# StackBreakoutConnection_4layers_V1_0_wit.net
KiCad netlist of a schematic drawn in EAGLE
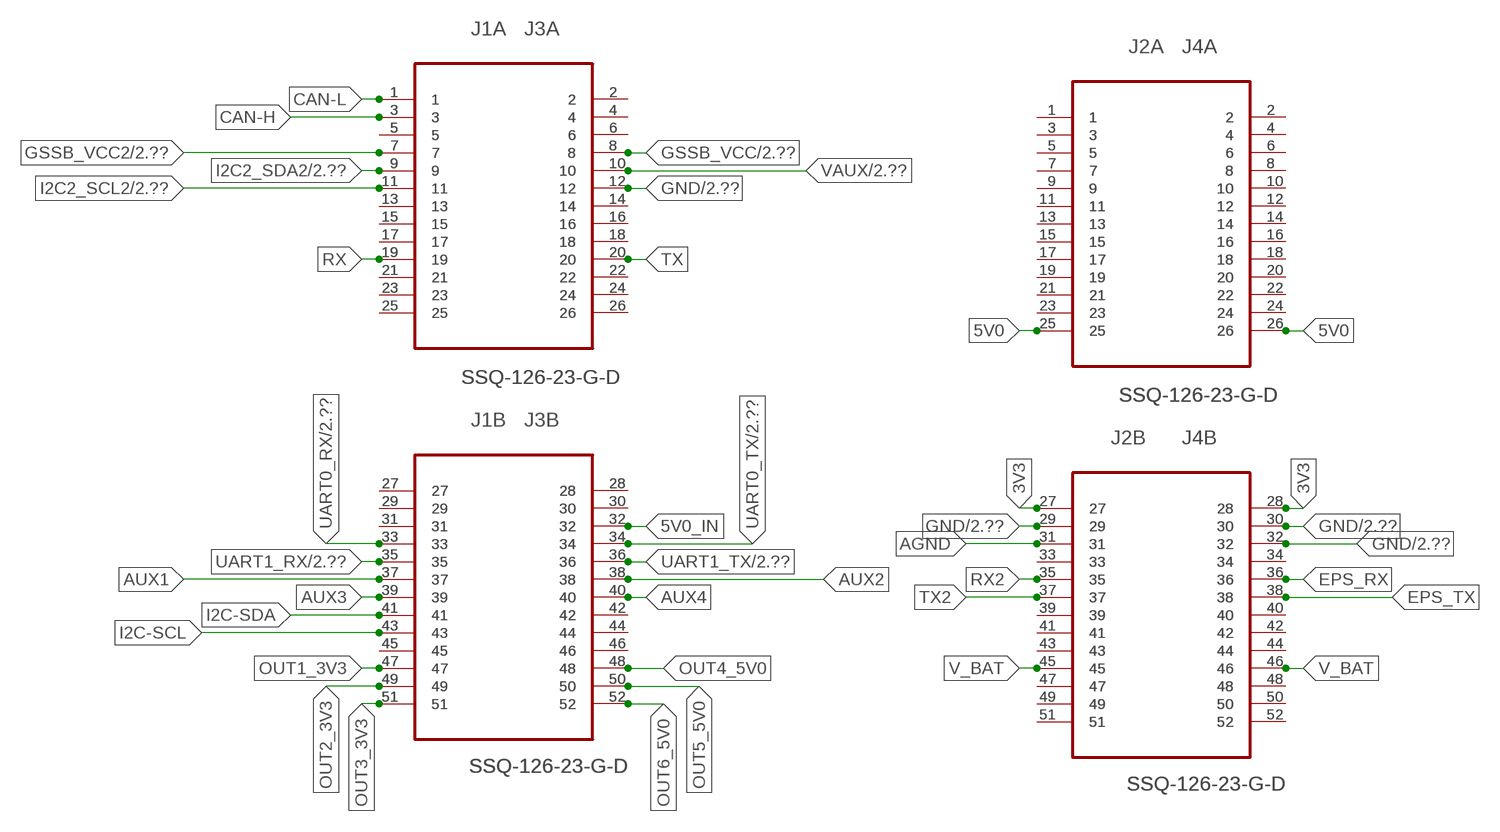
[diagram p0: schematic, sheet 1]
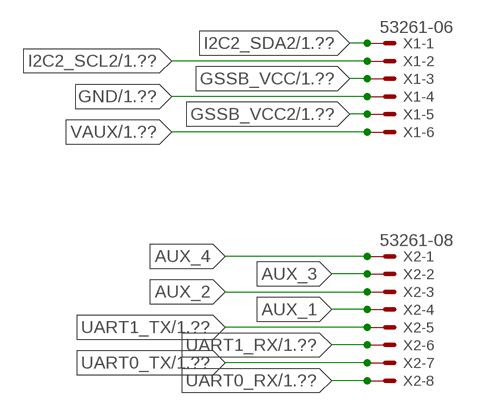
[diagram p1: schematic, sheet 2]

(export (version "E")
  (design (tool "Eeschema 10.0.6"))
  (components
    (comp (ref "X1")
      (value "53261-06")
      (footprint "eagle-import:53261-06")
      (fields (field (name "MF") "MOLEX"))
      (libsource (lib "eagle-import") (part "53?-06261"))
    )
    (comp (ref "X2")
      (value "53261-08")
      (footprint "eagle-import:53261-08")
      (fields (field (name "MF") "MOLEX"))
      (libsource (lib "eagle-import") (part "53?-08261"))
    )
    (comp (ref "J1")
      (value "SSQ-126-23-G-D")
      (footprint "eagle-import:SAMTEC_SSQ-126-23-G-D")
      (libsource (lib "eagle-import") (part "SSQ-126-23-G-D"))
    )
    (comp (ref "J2")
      (value "SSQ-126-23-G-D")
      (footprint "eagle-import:SAMTEC_SSQ-126-23-G-D")
      (libsource (lib "eagle-import") (part "SSQ-126-23-G-D"))
    )
    (comp (ref "J3")
      (value "SSQ-126-23-G-D")
      (footprint "eagle-import:SAMTEC_SSQ-126-23-G-D")
      (libsource (lib "eagle-import") (part "SSQ-126-23-G-D"))
    )
    (comp (ref "J4")
      (value "SSQ-126-23-G-D")
      (footprint "eagle-import:SAMTEC_SSQ-126-23-G-D")
      (libsource (lib "eagle-import") (part "SSQ-126-23-G-D"))
    )
  )
  (nets
    (net (code "1") (name "3V3") (class "Default")
      (node (ref "J2") (pin "27") (pinfunction "27_27") (pintype "passive"))
      (node (ref "J2") (pin "28") (pinfunction "28_28") (pintype "passive"))
      (node (ref "J4") (pin "27") (pinfunction "27_27") (pintype "passive"))
      (node (ref "J4") (pin "28") (pinfunction "28_28") (pintype "passive"))
    )
    (net (code "2") (name "5V0") (class "Default")
      (node (ref "J2") (pin "25") (pinfunction "25_25") (pintype "passive"))
      (node (ref "J2") (pin "26") (pinfunction "26_26") (pintype "passive"))
      (node (ref "J4") (pin "25") (pinfunction "25_25") (pintype "passive"))
      (node (ref "J4") (pin "26") (pinfunction "26_26") (pintype "passive"))
    )
    (net (code "3") (name "5V0_IN") (class "Default")
      (node (ref "J1") (pin "32") (pinfunction "32_32") (pintype "passive"))
      (node (ref "J3") (pin "32") (pinfunction "32_32") (pintype "passive"))
    )
    (net (code "4") (name "AGND") (class "Default")
      (node (ref "J2") (pin "31") (pinfunction "31_31") (pintype "passive"))
      (node (ref "J4") (pin "31") (pinfunction "31_31") (pintype "passive"))
    )
    (net (code "5") (name "AUX1") (class "Default")
      (node (ref "J1") (pin "37") (pinfunction "37_37") (pintype "passive"))
      (node (ref "J3") (pin "37") (pinfunction "37_37") (pintype "passive"))
    )
    (net (code "6") (name "AUX2") (class "Default")
      (node (ref "J1") (pin "38") (pinfunction "38_38") (pintype "passive"))
      (node (ref "J3") (pin "38") (pinfunction "38_38") (pintype "passive"))
    )
    (net (code "7") (name "AUX3") (class "Default")
      (node (ref "J1") (pin "39") (pinfunction "39_39") (pintype "passive"))
      (node (ref "J3") (pin "39") (pinfunction "39_39") (pintype "passive"))
    )
    (net (code "8") (name "AUX4") (class "Default")
      (node (ref "J1") (pin "40") (pinfunction "40_40") (pintype "passive"))
      (node (ref "J3") (pin "40") (pinfunction "40_40") (pintype "passive"))
    )
    (net (code "9") (name "AUX_1") (class "Default")
      (node (ref "X2") (pin "4") (pinfunction "S_4") (pintype "passive"))
    )
    (net (code "10") (name "AUX_2") (class "Default")
      (node (ref "X2") (pin "3") (pinfunction "S_3") (pintype "passive"))
    )
    (net (code "11") (name "AUX_3") (class "Default")
      (node (ref "X2") (pin "2") (pinfunction "S_2") (pintype "passive"))
    )
    (net (code "12") (name "AUX_4") (class "Default")
      (node (ref "X2") (pin "1") (pinfunction "S_1") (pintype "passive"))
    )
    (net (code "13") (name "CAN-H") (class "Default")
      (node (ref "J1") (pin "3") (pinfunction "3_3") (pintype "passive"))
      (node (ref "J3") (pin "3") (pinfunction "3_3") (pintype "passive"))
    )
    (net (code "14") (name "CAN-L") (class "Default")
      (node (ref "J1") (pin "1") (pinfunction "1_1") (pintype "passive"))
      (node (ref "J3") (pin "1") (pinfunction "1_1") (pintype "passive"))
    )
    (net (code "15") (name "EPS_RX") (class "Default")
      (node (ref "J2") (pin "36") (pinfunction "36_36") (pintype "passive"))
      (node (ref "J4") (pin "36") (pinfunction "36_36") (pintype "passive"))
    )
    (net (code "16") (name "EPS_TX") (class "Default")
      (node (ref "J2") (pin "38") (pinfunction "38_38") (pintype "passive"))
      (node (ref "J4") (pin "38") (pinfunction "38_38") (pintype "passive"))
    )
    (net (code "17") (name "GND") (class "Default")
      (node (ref "J1") (pin "12") (pinfunction "12_12") (pintype "passive"))
      (node (ref "J2") (pin "29") (pinfunction "29_29") (pintype "passive"))
      (node (ref "J2") (pin "30") (pinfunction "30_30") (pintype "passive"))
      (node (ref "J2") (pin "32") (pinfunction "32_32") (pintype "passive"))
      (node (ref "J3") (pin "12") (pinfunction "12_12") (pintype "passive"))
      (node (ref "J4") (pin "29") (pinfunction "29_29") (pintype "passive"))
      (node (ref "J4") (pin "30") (pinfunction "30_30") (pintype "passive"))
      (node (ref "J4") (pin "32") (pinfunction "32_32") (pintype "passive"))
      (node (ref "X1") (pin "4") (pinfunction "S_4") (pintype "passive"))
    )
    (net (code "18") (name "GSSB_VCC") (class "Default")
      (node (ref "J1") (pin "8") (pinfunction "8_8") (pintype "passive"))
      (node (ref "J3") (pin "8") (pinfunction "8_8") (pintype "passive"))
      (node (ref "X1") (pin "3") (pinfunction "S_3") (pintype "passive"))
    )
    (net (code "19") (name "GSSB_VCC2") (class "Default")
      (node (ref "J1") (pin "7") (pinfunction "7_7") (pintype "passive"))
      (node (ref "J3") (pin "7") (pinfunction "7_7") (pintype "passive"))
      (node (ref "X1") (pin "5") (pinfunction "S_5") (pintype "passive"))
    )
    (net (code "20") (name "I2C-SCL") (class "Default")
      (node (ref "J1") (pin "43") (pinfunction "43_43") (pintype "passive"))
      (node (ref "J3") (pin "43") (pinfunction "43_43") (pintype "passive"))
    )
    (net (code "21") (name "I2C-SDA") (class "Default")
      (node (ref "J1") (pin "41") (pinfunction "41_41") (pintype "passive"))
      (node (ref "J3") (pin "41") (pinfunction "41_41") (pintype "passive"))
    )
    (net (code "22") (name "I2C2_SCL2") (class "Default")
      (node (ref "J1") (pin "11") (pinfunction "11_11") (pintype "passive"))
      (node (ref "J3") (pin "11") (pinfunction "11_11") (pintype "passive"))
      (node (ref "X1") (pin "2") (pinfunction "S_2") (pintype "passive"))
    )
    (net (code "23") (name "I2C2_SDA2") (class "Default")
      (node (ref "J1") (pin "9") (pinfunction "9_9") (pintype "passive"))
      (node (ref "J3") (pin "9") (pinfunction "9_9") (pintype "passive"))
      (node (ref "X1") (pin "1") (pinfunction "S_1") (pintype "passive"))
    )
    (net (code "24") (name "Net-(J1-Pad2)") (class "Default")
      (node (ref "J1") (pin "2") (pinfunction "2_2") (pintype "passive"))
      (node (ref "J3") (pin "2") (pinfunction "2_2") (pintype "passive"))
    )
    (net (code "25") (name "Net-(J1-Pad4)") (class "Default")
      (node (ref "J1") (pin "4") (pinfunction "4_4") (pintype "passive"))
      (node (ref "J3") (pin "4") (pinfunction "4_4") (pintype "passive"))
    )
    (net (code "26") (name "Net-(J1-Pad5)") (class "Default")
      (node (ref "J1") (pin "5") (pinfunction "5_5") (pintype "passive"))
      (node (ref "J3") (pin "5") (pinfunction "5_5") (pintype "passive"))
    )
    (net (code "27") (name "Net-(J1-Pad6)") (class "Default")
      (node (ref "J1") (pin "6") (pinfunction "6_6") (pintype "passive"))
      (node (ref "J3") (pin "6") (pinfunction "6_6") (pintype "passive"))
    )
    (net (code "28") (name "Net-(J1-Pad13)") (class "Default")
      (node (ref "J1") (pin "13") (pinfunction "13_13") (pintype "passive"))
      (node (ref "J3") (pin "13") (pinfunction "13_13") (pintype "passive"))
    )
    (net (code "29") (name "Net-(J1-Pad14)") (class "Default")
      (node (ref "J1") (pin "14") (pinfunction "14_14") (pintype "passive"))
      (node (ref "J3") (pin "14") (pinfunction "14_14") (pintype "passive"))
    )
    (net (code "30") (name "Net-(J1-Pad15)") (class "Default")
      (node (ref "J1") (pin "15") (pinfunction "15_15") (pintype "passive"))
      (node (ref "J3") (pin "15") (pinfunction "15_15") (pintype "passive"))
    )
    (net (code "31") (name "Net-(J1-Pad16)") (class "Default")
      (node (ref "J1") (pin "16") (pinfunction "16_16") (pintype "passive"))
      (node (ref "J3") (pin "16") (pinfunction "16_16") (pintype "passive"))
    )
    (net (code "32") (name "Net-(J1-Pad17)") (class "Default")
      (node (ref "J1") (pin "17") (pinfunction "17_17") (pintype "passive"))
      (node (ref "J3") (pin "17") (pinfunction "17_17") (pintype "passive"))
    )
    (net (code "33") (name "Net-(J1-Pad18)") (class "Default")
      (node (ref "J1") (pin "18") (pinfunction "18_18") (pintype "passive"))
      (node (ref "J3") (pin "18") (pinfunction "18_18") (pintype "passive"))
    )
    (net (code "34") (name "Net-(J1-Pad21)") (class "Default")
      (node (ref "J1") (pin "21") (pinfunction "21_21") (pintype "passive"))
      (node (ref "J3") (pin "21") (pinfunction "21_21") (pintype "passive"))
    )
    (net (code "35") (name "Net-(J1-Pad22)") (class "Default")
      (node (ref "J1") (pin "22") (pinfunction "22_22") (pintype "passive"))
      (node (ref "J3") (pin "22") (pinfunction "22_22") (pintype "passive"))
    )
    (net (code "36") (name "Net-(J1-Pad23)") (class "Default")
      (node (ref "J1") (pin "23") (pinfunction "23_23") (pintype "passive"))
      (node (ref "J3") (pin "23") (pinfunction "23_23") (pintype "passive"))
    )
    (net (code "37") (name "Net-(J1-Pad24)") (class "Default")
      (node (ref "J1") (pin "24") (pinfunction "24_24") (pintype "passive"))
      (node (ref "J3") (pin "24") (pinfunction "24_24") (pintype "passive"))
    )
    (net (code "38") (name "Net-(J1-Pad25)") (class "Default")
      (node (ref "J1") (pin "25") (pinfunction "25_25") (pintype "passive"))
      (node (ref "J3") (pin "25") (pinfunction "25_25") (pintype "passive"))
    )
    (net (code "39") (name "Net-(J1-Pad26)") (class "Default")
      (node (ref "J1") (pin "26") (pinfunction "26_26") (pintype "passive"))
      (node (ref "J3") (pin "26") (pinfunction "26_26") (pintype "passive"))
    )
    (net (code "40") (name "Net-(J1-Pad27)") (class "Default")
      (node (ref "J1") (pin "27") (pinfunction "27_27") (pintype "passive"))
      (node (ref "J3") (pin "27") (pinfunction "27_27") (pintype "passive"))
    )
    (net (code "41") (name "Net-(J1-Pad28)") (class "Default")
      (node (ref "J1") (pin "28") (pinfunction "28_28") (pintype "passive"))
      (node (ref "J3") (pin "28") (pinfunction "28_28") (pintype "passive"))
    )
    (net (code "42") (name "Net-(J1-Pad29)") (class "Default")
      (node (ref "J1") (pin "29") (pinfunction "29_29") (pintype "passive"))
      (node (ref "J3") (pin "29") (pinfunction "29_29") (pintype "passive"))
    )
    (net (code "43") (name "Net-(J1-Pad30)") (class "Default")
      (node (ref "J1") (pin "30") (pinfunction "30_30") (pintype "passive"))
      (node (ref "J3") (pin "30") (pinfunction "30_30") (pintype "passive"))
    )
    (net (code "44") (name "Net-(J1-Pad31)") (class "Default")
      (node (ref "J1") (pin "31") (pinfunction "31_31") (pintype "passive"))
      (node (ref "J3") (pin "31") (pinfunction "31_31") (pintype "passive"))
    )
    (net (code "45") (name "Net-(J1-Pad42)") (class "Default")
      (node (ref "J1") (pin "42") (pinfunction "42_42") (pintype "passive"))
      (node (ref "J3") (pin "42") (pinfunction "42_42") (pintype "passive"))
    )
    (net (code "46") (name "Net-(J1-Pad44)") (class "Default")
      (node (ref "J1") (pin "44") (pinfunction "44_44") (pintype "passive"))
      (node (ref "J3") (pin "44") (pinfunction "44_44") (pintype "passive"))
    )
    (net (code "47") (name "Net-(J1-Pad45)") (class "Default")
      (node (ref "J1") (pin "45") (pinfunction "45_45") (pintype "passive"))
      (node (ref "J3") (pin "45") (pinfunction "45_45") (pintype "passive"))
    )
    (net (code "48") (name "Net-(J1-Pad46)") (class "Default")
      (node (ref "J1") (pin "46") (pinfunction "46_46") (pintype "passive"))
      (node (ref "J3") (pin "46") (pinfunction "46_46") (pintype "passive"))
    )
    (net (code "49") (name "Net-(J2-Pad1)") (class "Default")
      (node (ref "J2") (pin "1") (pinfunction "1_1") (pintype "passive"))
      (node (ref "J4") (pin "1") (pinfunction "1_1") (pintype "passive"))
    )
    (net (code "50") (name "Net-(J2-Pad2)") (class "Default")
      (node (ref "J2") (pin "2") (pinfunction "2_2") (pintype "passive"))
      (node (ref "J4") (pin "2") (pinfunction "2_2") (pintype "passive"))
    )
    (net (code "51") (name "Net-(J2-Pad3)") (class "Default")
      (node (ref "J2") (pin "3") (pinfunction "3_3") (pintype "passive"))
      (node (ref "J4") (pin "3") (pinfunction "3_3") (pintype "passive"))
    )
    (net (code "52") (name "Net-(J2-Pad4)") (class "Default")
      (node (ref "J2") (pin "4") (pinfunction "4_4") (pintype "passive"))
      (node (ref "J4") (pin "4") (pinfunction "4_4") (pintype "passive"))
    )
    (net (code "53") (name "Net-(J2-Pad5)") (class "Default")
      (node (ref "J2") (pin "5") (pinfunction "5_5") (pintype "passive"))
      (node (ref "J4") (pin "5") (pinfunction "5_5") (pintype "passive"))
    )
    (net (code "54") (name "Net-(J2-Pad6)") (class "Default")
      (node (ref "J2") (pin "6") (pinfunction "6_6") (pintype "passive"))
      (node (ref "J4") (pin "6") (pinfunction "6_6") (pintype "passive"))
    )
    (net (code "55") (name "Net-(J2-Pad7)") (class "Default")
      (node (ref "J2") (pin "7") (pinfunction "7_7") (pintype "passive"))
      (node (ref "J4") (pin "7") (pinfunction "7_7") (pintype "passive"))
    )
    (net (code "56") (name "Net-(J2-Pad8)") (class "Default")
      (node (ref "J2") (pin "8") (pinfunction "8_8") (pintype "passive"))
      (node (ref "J4") (pin "8") (pinfunction "8_8") (pintype "passive"))
    )
    (net (code "57") (name "Net-(J2-Pad9)") (class "Default")
      (node (ref "J2") (pin "9") (pinfunction "9_9") (pintype "passive"))
      (node (ref "J4") (pin "9") (pinfunction "9_9") (pintype "passive"))
    )
    (net (code "58") (name "Net-(J2-Pad10)") (class "Default")
      (node (ref "J2") (pin "10") (pinfunction "10_10") (pintype "passive"))
      (node (ref "J4") (pin "10") (pinfunction "10_10") (pintype "passive"))
    )
    (net (code "59") (name "Net-(J2-Pad11)") (class "Default")
      (node (ref "J2") (pin "11") (pinfunction "11_11") (pintype "passive"))
      (node (ref "J4") (pin "11") (pinfunction "11_11") (pintype "passive"))
    )
    (net (code "60") (name "Net-(J2-Pad12)") (class "Default")
      (node (ref "J2") (pin "12") (pinfunction "12_12") (pintype "passive"))
      (node (ref "J4") (pin "12") (pinfunction "12_12") (pintype "passive"))
    )
    (net (code "61") (name "Net-(J2-Pad13)") (class "Default")
      (node (ref "J2") (pin "13") (pinfunction "13_13") (pintype "passive"))
      (node (ref "J4") (pin "13") (pinfunction "13_13") (pintype "passive"))
    )
    (net (code "62") (name "Net-(J2-Pad14)") (class "Default")
      (node (ref "J2") (pin "14") (pinfunction "14_14") (pintype "passive"))
      (node (ref "J4") (pin "14") (pinfunction "14_14") (pintype "passive"))
    )
    (net (code "63") (name "Net-(J2-Pad15)") (class "Default")
      (node (ref "J2") (pin "15") (pinfunction "15_15") (pintype "passive"))
      (node (ref "J4") (pin "15") (pinfunction "15_15") (pintype "passive"))
    )
    (net (code "64") (name "Net-(J2-Pad16)") (class "Default")
      (node (ref "J2") (pin "16") (pinfunction "16_16") (pintype "passive"))
      (node (ref "J4") (pin "16") (pinfunction "16_16") (pintype "passive"))
    )
    (net (code "65") (name "Net-(J2-Pad17)") (class "Default")
      (node (ref "J2") (pin "17") (pinfunction "17_17") (pintype "passive"))
      (node (ref "J4") (pin "17") (pinfunction "17_17") (pintype "passive"))
    )
    (net (code "66") (name "Net-(J2-Pad18)") (class "Default")
      (node (ref "J2") (pin "18") (pinfunction "18_18") (pintype "passive"))
      (node (ref "J4") (pin "18") (pinfunction "18_18") (pintype "passive"))
    )
    (net (code "67") (name "Net-(J2-Pad19)") (class "Default")
      (node (ref "J2") (pin "19") (pinfunction "19_19") (pintype "passive"))
      (node (ref "J4") (pin "19") (pinfunction "19_19") (pintype "passive"))
    )
    (net (code "68") (name "Net-(J2-Pad20)") (class "Default")
      (node (ref "J2") (pin "20") (pinfunction "20_20") (pintype "passive"))
      (node (ref "J4") (pin "20") (pinfunction "20_20") (pintype "passive"))
    )
    (net (code "69") (name "Net-(J2-Pad21)") (class "Default")
      (node (ref "J2") (pin "21") (pinfunction "21_21") (pintype "passive"))
      (node (ref "J4") (pin "21") (pinfunction "21_21") (pintype "passive"))
    )
    (net (code "70") (name "Net-(J2-Pad22)") (class "Default")
      (node (ref "J2") (pin "22") (pinfunction "22_22") (pintype "passive"))
      (node (ref "J4") (pin "22") (pinfunction "22_22") (pintype "passive"))
    )
    (net (code "71") (name "Net-(J2-Pad23)") (class "Default")
      (node (ref "J2") (pin "23") (pinfunction "23_23") (pintype "passive"))
      (node (ref "J4") (pin "23") (pinfunction "23_23") (pintype "passive"))
    )
    (net (code "72") (name "Net-(J2-Pad24)") (class "Default")
      (node (ref "J2") (pin "24") (pinfunction "24_24") (pintype "passive"))
      (node (ref "J4") (pin "24") (pinfunction "24_24") (pintype "passive"))
    )
    (net (code "73") (name "Net-(J2-Pad33)") (class "Default")
      (node (ref "J2") (pin "33") (pinfunction "33_33") (pintype "passive"))
      (node (ref "J4") (pin "33") (pinfunction "33_33") (pintype "passive"))
    )
    (net (code "74") (name "Net-(J2-Pad34)") (class "Default")
      (node (ref "J2") (pin "34") (pinfunction "34_34") (pintype "passive"))
      (node (ref "J4") (pin "34") (pinfunction "34_34") (pintype "passive"))
    )
    (net (code "75") (name "Net-(J2-Pad39)") (class "Default")
      (node (ref "J2") (pin "39") (pinfunction "39_39") (pintype "passive"))
      (node (ref "J4") (pin "39") (pinfunction "39_39") (pintype "passive"))
    )
    (net (code "76") (name "Net-(J2-Pad40)") (class "Default")
      (node (ref "J2") (pin "40") (pinfunction "40_40") (pintype "passive"))
      (node (ref "J4") (pin "40") (pinfunction "40_40") (pintype "passive"))
    )
    (net (code "77") (name "Net-(J2-Pad41)") (class "Default")
      (node (ref "J2") (pin "41") (pinfunction "41_41") (pintype "passive"))
      (node (ref "J4") (pin "41") (pinfunction "41_41") (pintype "passive"))
    )
    (net (code "78") (name "Net-(J2-Pad42)") (class "Default")
      (node (ref "J2") (pin "42") (pinfunction "42_42") (pintype "passive"))
      (node (ref "J4") (pin "42") (pinfunction "42_42") (pintype "passive"))
    )
    (net (code "79") (name "Net-(J2-Pad43)") (class "Default")
      (node (ref "J2") (pin "43") (pinfunction "43_43") (pintype "passive"))
      (node (ref "J4") (pin "43") (pinfunction "43_43") (pintype "passive"))
    )
    (net (code "80") (name "Net-(J2-Pad44)") (class "Default")
      (node (ref "J2") (pin "44") (pinfunction "44_44") (pintype "passive"))
      (node (ref "J4") (pin "44") (pinfunction "44_44") (pintype "passive"))
    )
    (net (code "81") (name "Net-(J2-Pad47)") (class "Default")
      (node (ref "J2") (pin "47") (pinfunction "47_47") (pintype "passive"))
      (node (ref "J4") (pin "47") (pinfunction "47_47") (pintype "passive"))
    )
    (net (code "82") (name "Net-(J2-Pad48)") (class "Default")
      (node (ref "J2") (pin "48") (pinfunction "48_48") (pintype "passive"))
      (node (ref "J4") (pin "48") (pinfunction "48_48") (pintype "passive"))
    )
    (net (code "83") (name "Net-(J2-Pad49)") (class "Default")
      (node (ref "J2") (pin "49") (pinfunction "49_49") (pintype "passive"))
      (node (ref "J4") (pin "49") (pinfunction "49_49") (pintype "passive"))
    )
    (net (code "84") (name "Net-(J2-Pad50)") (class "Default")
      (node (ref "J2") (pin "50") (pinfunction "50_50") (pintype "passive"))
      (node (ref "J4") (pin "50") (pinfunction "50_50") (pintype "passive"))
    )
    (net (code "85") (name "Net-(J2-Pad51)") (class "Default")
      (node (ref "J2") (pin "51") (pinfunction "51_51") (pintype "passive"))
      (node (ref "J4") (pin "51") (pinfunction "51_51") (pintype "passive"))
    )
    (net (code "86") (name "Net-(J2-Pad52)") (class "Default")
      (node (ref "J2") (pin "52") (pinfunction "52_52") (pintype "passive"))
      (node (ref "J4") (pin "52") (pinfunction "52_52") (pintype "passive"))
    )
    (net (code "87") (name "OUT1_3V3") (class "Default")
      (node (ref "J1") (pin "47") (pinfunction "47_47") (pintype "passive"))
      (node (ref "J3") (pin "47") (pinfunction "47_47") (pintype "passive"))
    )
    (net (code "88") (name "OUT2_3V3") (class "Default")
      (node (ref "J1") (pin "49") (pinfunction "49_49") (pintype "passive"))
      (node (ref "J3") (pin "49") (pinfunction "49_49") (pintype "passive"))
    )
    (net (code "89") (name "OUT3_3V3") (class "Default")
      (node (ref "J1") (pin "51") (pinfunction "51_51") (pintype "passive"))
      (node (ref "J3") (pin "51") (pinfunction "51_51") (pintype "passive"))
    )
    (net (code "90") (name "OUT4_5V0") (class "Default")
      (node (ref "J1") (pin "48") (pinfunction "48_48") (pintype "passive"))
      (node (ref "J3") (pin "48") (pinfunction "48_48") (pintype "passive"))
    )
    (net (code "91") (name "OUT5_5V0") (class "Default")
      (node (ref "J1") (pin "50") (pinfunction "50_50") (pintype "passive"))
      (node (ref "J3") (pin "50") (pinfunction "50_50") (pintype "passive"))
    )
    (net (code "92") (name "OUT6_5V0") (class "Default")
      (node (ref "J1") (pin "52") (pinfunction "52_52") (pintype "passive"))
      (node (ref "J3") (pin "52") (pinfunction "52_52") (pintype "passive"))
    )
    (net (code "93") (name "RX") (class "Default")
      (node (ref "J1") (pin "19") (pinfunction "19_19") (pintype "passive"))
      (node (ref "J3") (pin "19") (pinfunction "19_19") (pintype "passive"))
    )
    (net (code "94") (name "RX2") (class "Default")
      (node (ref "J2") (pin "35") (pinfunction "35_35") (pintype "passive"))
      (node (ref "J4") (pin "35") (pinfunction "35_35") (pintype "passive"))
    )
    (net (code "95") (name "TX") (class "Default")
      (node (ref "J1") (pin "20") (pinfunction "20_20") (pintype "passive"))
      (node (ref "J3") (pin "20") (pinfunction "20_20") (pintype "passive"))
    )
    (net (code "96") (name "TX2") (class "Default")
      (node (ref "J2") (pin "37") (pinfunction "37_37") (pintype "passive"))
      (node (ref "J4") (pin "37") (pinfunction "37_37") (pintype "passive"))
    )
    (net (code "97") (name "UART0_RX") (class "Default")
      (node (ref "J1") (pin "33") (pinfunction "33_33") (pintype "passive"))
      (node (ref "J3") (pin "33") (pinfunction "33_33") (pintype "passive"))
      (node (ref "X2") (pin "8") (pinfunction "S_8") (pintype "passive"))
    )
    (net (code "98") (name "UART0_TX") (class "Default")
      (node (ref "J1") (pin "34") (pinfunction "34_34") (pintype "passive"))
      (node (ref "J3") (pin "34") (pinfunction "34_34") (pintype "passive"))
      (node (ref "X2") (pin "7") (pinfunction "S_7") (pintype "passive"))
    )
    (net (code "99") (name "UART1_RX") (class "Default")
      (node (ref "J1") (pin "35") (pinfunction "35_35") (pintype "passive"))
      (node (ref "J3") (pin "35") (pinfunction "35_35") (pintype "passive"))
      (node (ref "X2") (pin "6") (pinfunction "S_6") (pintype "passive"))
    )
    (net (code "100") (name "UART1_TX") (class "Default")
      (node (ref "J1") (pin "36") (pinfunction "36_36") (pintype "passive"))
      (node (ref "J3") (pin "36") (pinfunction "36_36") (pintype "passive"))
      (node (ref "X2") (pin "5") (pinfunction "S_5") (pintype "passive"))
    )
    (net (code "101") (name "VAUX") (class "Default")
      (node (ref "J1") (pin "10") (pinfunction "10_10") (pintype "passive"))
      (node (ref "J3") (pin "10") (pinfunction "10_10") (pintype "passive"))
      (node (ref "X1") (pin "6") (pinfunction "S_6") (pintype "passive"))
    )
    (net (code "102") (name "V_BAT") (class "Default")
      (node (ref "J2") (pin "45") (pinfunction "45_45") (pintype "passive"))
      (node (ref "J2") (pin "46") (pinfunction "46_46") (pintype "passive"))
      (node (ref "J4") (pin "45") (pinfunction "45_45") (pintype "passive"))
      (node (ref "J4") (pin "46") (pinfunction "46_46") (pintype "passive"))
    )
  )
)
